# Adafruit_MicroLipo_Charger_v2.net
KiCad netlist of a schematic drawn in EAGLE
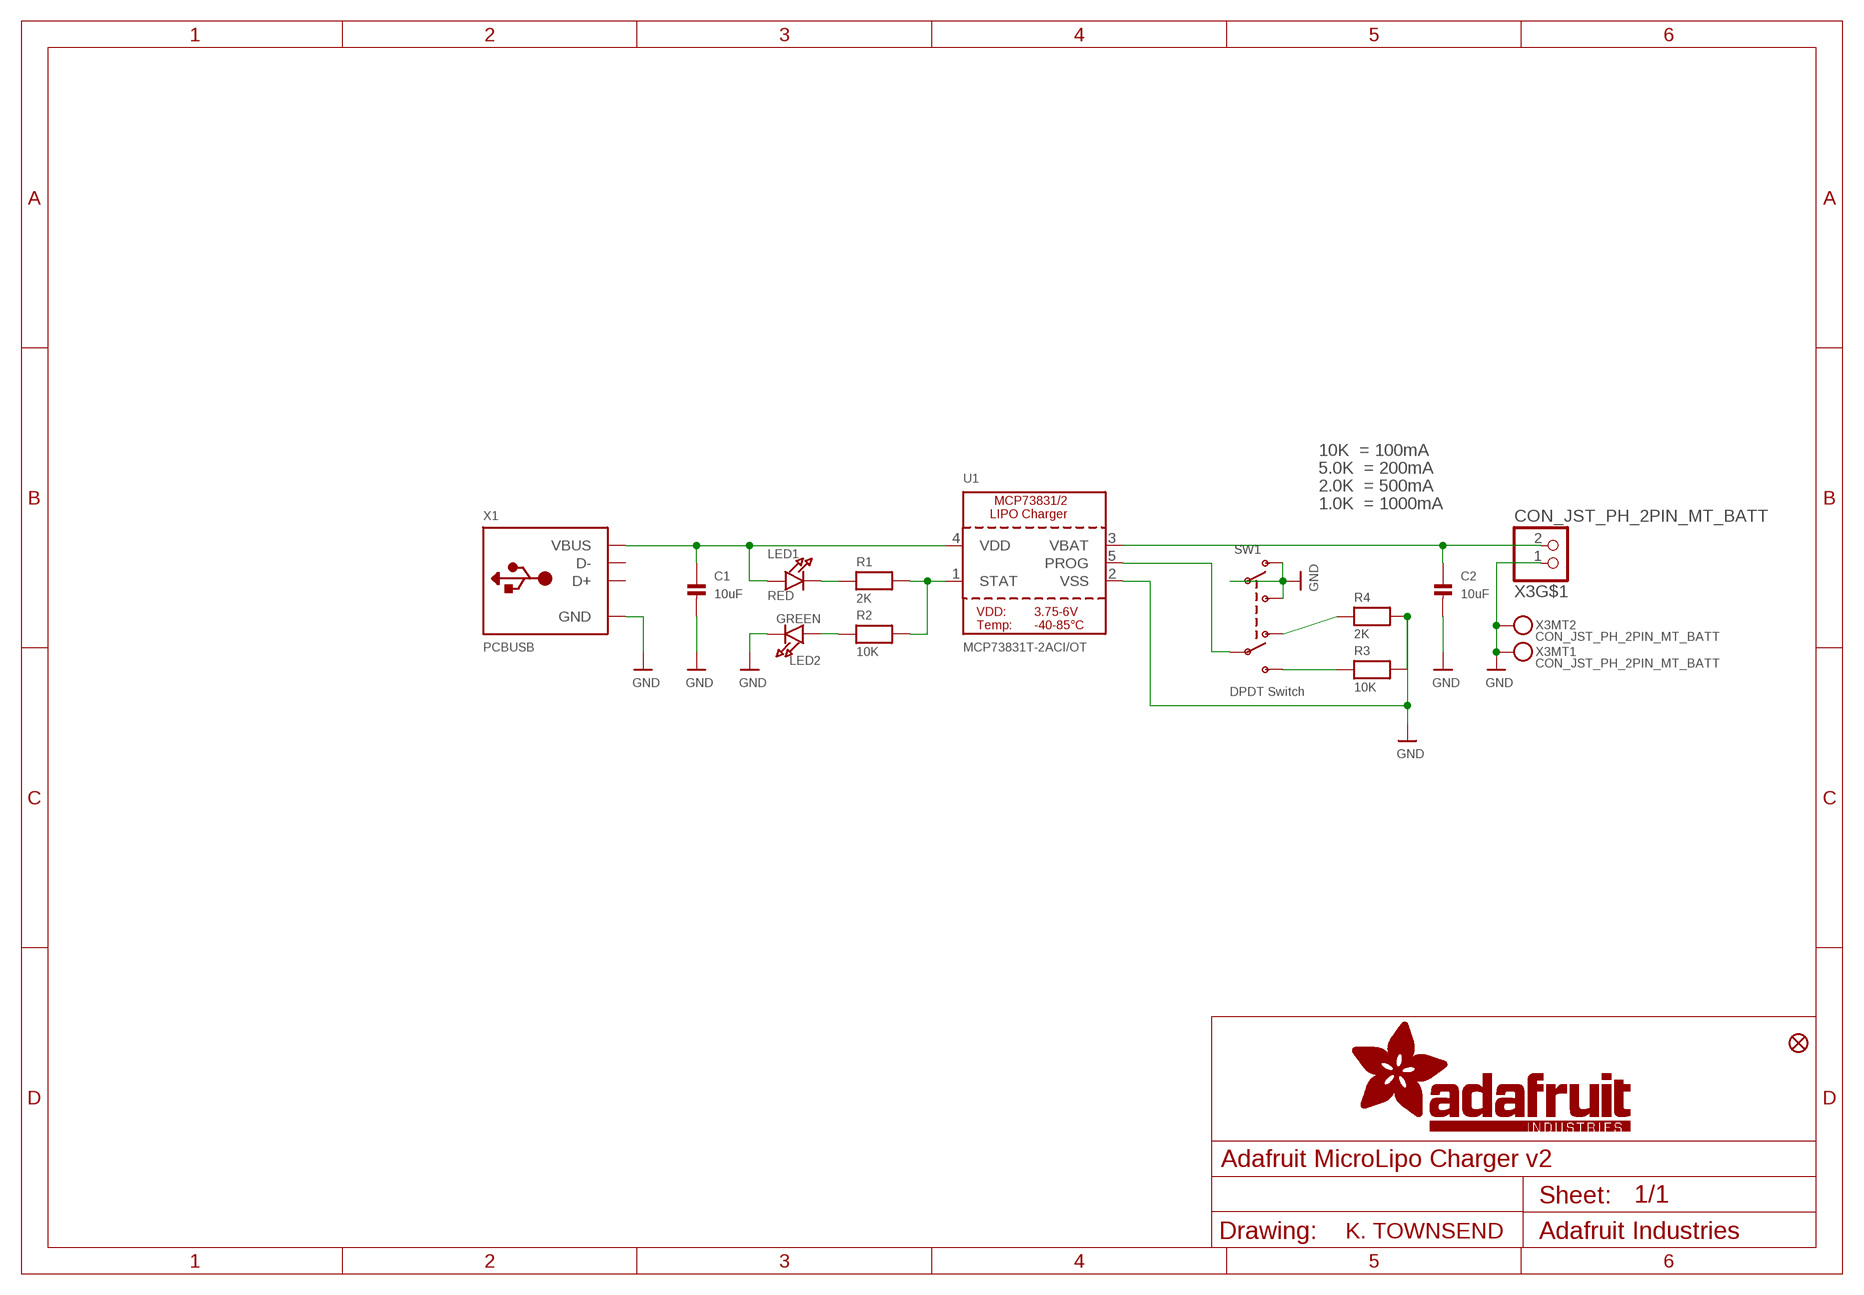
[diagram p0: schematic, sheet 1]

(export (version "E")
  (design (tool "Eeschema 10.0.6"))
  (components
    (comp (ref "C1")
      (value "10uF")
      (footprint "eagle-import:0805-NO")
      (libsource (lib "eagle-import") (part "CAP_CERAMIC0805-NOOUTLINE"))
    )
    (comp (ref "C2")
      (value "10uF")
      (footprint "eagle-import:0805-NO")
      (libsource (lib "eagle-import") (part "CAP_CERAMIC0805-NOOUTLINE"))
    )
    (comp (ref "FID1")
      (value "FIDUCIAL_1MM")
      (footprint "eagle-import:FIDUCIAL_1MM")
      (libsource (lib "eagle-import") (part "FIDUCIAL_1MM"))
    )
    (comp (ref "LED1")
      (value "RED")
      (footprint "eagle-import:CHIPLED_0603_NOOUTLINE")
      (libsource (lib "eagle-import") (part "LED0603_NOOUTLINE"))
    )
    (comp (ref "LED2")
      (value "GREEN")
      (footprint "eagle-import:CHIPLED_0603_NOOUTLINE")
      (libsource (lib "eagle-import") (part "LED0603_NOOUTLINE"))
    )
    (comp (ref "R1")
      (value "2K")
      (footprint "eagle-import:0603-NO")
      (libsource (lib "eagle-import") (part "RESISTOR_0603_NOOUT"))
    )
    (comp (ref "R2")
      (value "10K")
      (footprint "eagle-import:0603-NO")
      (libsource (lib "eagle-import") (part "RESISTOR_0603_NOOUT"))
    )
    (comp (ref "R3")
      (value "10K")
      (footprint "eagle-import:0603-NO")
      (libsource (lib "eagle-import") (part "RESISTOR_0603_NOOUT"))
    )
    (comp (ref "R4")
      (value "2K")
      (footprint "eagle-import:0603-NO")
      (libsource (lib "eagle-import") (part "RESISTOR_0603_NOOUT"))
    )
    (comp (ref "SW1")
      (value "DPDT Switch")
      (footprint "eagle-import:EG1390")
      (libsource (lib "eagle-import") (part "SWITCH_DPDTEG1390"))
    )
    (comp (ref "U1")
      (value "MCP73831T-2ACI/OT")
      (footprint "eagle-import:SOT23-5")
      (libsource (lib "eagle-import") (part "MCP73831/2"))
    )
    (comp (ref "X1")
      (value "PCBUSB")
      (footprint "eagle-import:USBA_PCB")
      (libsource (lib "eagle-import") (part "USB_TYPEAPCB"))
    )
    (comp (ref "X3")
      (value "CON_JST_PH_2PIN_MT_BATT")
      (footprint "eagle-import:JSTPH2_BATT")
      (libsource (lib "eagle-import") (part "CON_JST_PH_2PIN_MT_BATT"))
    )
  )
  (nets
    (net (code "1") (name "GND") (class "Default")
      (node (ref "C1") (pin "2") (pinfunction "2_2") (pintype "passive"))
      (node (ref "C2") (pin "2") (pinfunction "2_2") (pintype "passive"))
      (node (ref "LED2") (pin "C") (pinfunction "C_C") (pintype "passive"))
      (node (ref "R3") (pin "2") (pinfunction "2_2") (pintype "passive"))
      (node (ref "R4") (pin "2") (pinfunction "2_2") (pintype "passive"))
      (node (ref "SW1") (pin "O1") (pinfunction "O1_O1") (pintype "passive"))
      (node (ref "SW1") (pin "P1") (pinfunction "P1_P1") (pintype "passive"))
      (node (ref "SW1") (pin "S1") (pinfunction "S1_S1") (pintype "passive"))
      (node (ref "U1") (pin "2") (pinfunction "VSS_2") (pintype "power_in"))
      (node (ref "X1") (pin "GND") (pinfunction "GND_GND") (pintype "power_in"))
      (node (ref "X3") (pin "1") (pinfunction "1_1") (pintype "passive"))
      (node (ref "X3") (pin "NC1") (pinfunction "P$1_NC1") (pintype "bidirectional"))
      (node (ref "X3") (pin "NC2") (pinfunction "P$1_NC2") (pintype "bidirectional"))
    )
    (net (code "2") (name "Net-(LED1-PadC)") (class "Default")
      (node (ref "LED1") (pin "C") (pinfunction "C_C") (pintype "passive"))
      (node (ref "R1") (pin "1") (pinfunction "1_1") (pintype "passive"))
    )
    (net (code "3") (name "Net-(LED2-PadA)") (class "Default")
      (node (ref "LED2") (pin "A") (pinfunction "A_A") (pintype "passive"))
      (node (ref "R2") (pin "1") (pinfunction "1_1") (pintype "passive"))
    )
    (net (code "4") (name "Net-(R3-Pad1)") (class "Default")
      (node (ref "R3") (pin "1") (pinfunction "1_1") (pintype "passive"))
      (node (ref "SW1") (pin "S2") (pinfunction "S2_S2") (pintype "passive"))
    )
    (net (code "5") (name "Net-(R4-Pad1)") (class "Default")
      (node (ref "R4") (pin "1") (pinfunction "1_1") (pintype "passive"))
      (node (ref "SW1") (pin "O2") (pinfunction "O2_O2") (pintype "passive"))
    )
    (net (code "6") (name "Net-(U1-PROG)") (class "Default")
      (node (ref "SW1") (pin "P2") (pinfunction "P2_P2") (pintype "passive"))
      (node (ref "U1") (pin "5") (pinfunction "PROG_5") (pintype "input"))
    )
    (net (code "7") (name "Net-(U1-STAT)") (class "Default")
      (node (ref "R1") (pin "2") (pinfunction "2_2") (pintype "passive"))
      (node (ref "R2") (pin "2") (pinfunction "2_2") (pintype "passive"))
      (node (ref "U1") (pin "1") (pinfunction "STAT_1") (pintype "output"))
    )
    (net (code "8") (name "Net-(U1-VBAT)") (class "Default")
      (node (ref "C2") (pin "1") (pinfunction "1_1") (pintype "passive"))
      (node (ref "U1") (pin "3") (pinfunction "VBAT_3") (pintype "power_in"))
      (node (ref "X3") (pin "2") (pinfunction "2_2") (pintype "passive"))
    )
    (net (code "9") (name "Net-(U1-VDD)") (class "Default")
      (node (ref "C1") (pin "1") (pinfunction "1_1") (pintype "passive"))
      (node (ref "LED1") (pin "A") (pinfunction "A_A") (pintype "passive"))
      (node (ref "U1") (pin "4") (pinfunction "VDD_4") (pintype "power_in"))
      (node (ref "X1") (pin "VCC") (pinfunction "VBUS_VCC") (pintype "power_in"))
    )
    (net (code "10") (name "unconnected-(X1-D+-PadUSB_PLUS)") (class "Default")
      (node (ref "X1") (pin "USB_PLUS") (pinfunction "D+_USB_PLUS") (pintype "bidirectional"))
    )
    (net (code "11") (name "unconnected-(X1-D--PadUSB_NEG)") (class "Default")
      (node (ref "X1") (pin "USB_NEG") (pinfunction "D-_USB_NEG") (pintype "bidirectional"))
    )
  )
)
